# FPGA_Config.net
KiCad netlist of a schematic drawn in Altium Designer
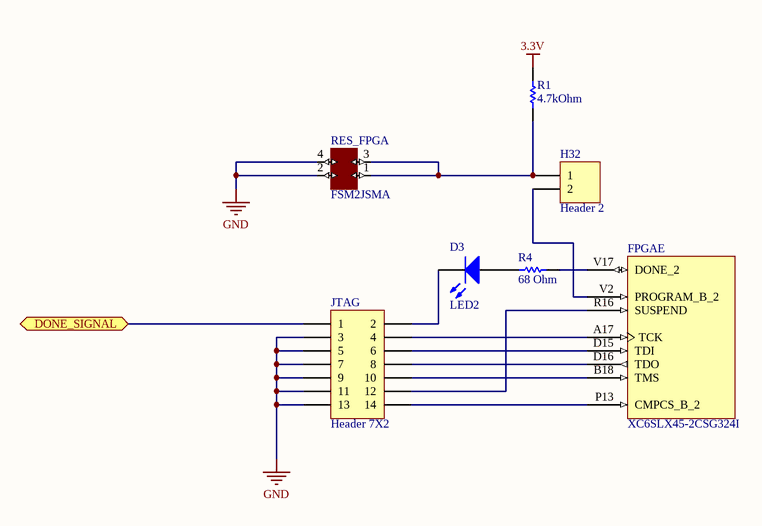
[diagram p0: FPGA Config.SchDoc]

(export (version "E")
  (design (tool "Eeschema 10.0.6"))
  (components
    (comp (ref "D3")
      (value "LED2")
      (footprint "3.2X1.6X1.1")
      (description "Typical RED, GREEN, YELLOW, AMBER GaAs LED")
      (fields (field (name "PUBLISHER") "Altium Limited"))
      (libsource (lib "Miscellaneous Devices") (part "LED2"))
    )
    (comp (ref "FPGA")
      (value "XC6SLX45-2CSG324I")
      (footprint "CSG324")
      (fields (field (name "PUBLISHER") "Altium Limited"))
      (libsource (lib "Xilinx Spartan-6") (part "XC6SLX45-2CSG324I"))
    )
    (comp (ref "H32")
      (value "Header 2")
      (footprint "HDR1X2")
      (description "Header, 2-Pin")
      (fields (field (name "PUBLISHER") "Altium Limited"))
      (libsource (lib "Miscellaneous Connectors") (part "Header 2"))
    )
    (comp (ref "JTAG")
      (value "Header 7X2")
      (footprint "HDR2X7")
      (description "Header, 7-Pin, Dual row")
      (fields (field (name "PUBLISHER") "Altium Limited"))
      (libsource (lib "Miscellaneous Connectors") (part "Header 7X2"))
    )
    (comp (ref "R1")
      (value "4.7kOhm")
      (footprint "RESC0603(1608)_M")
      (description "1R 0.1W 5% 0603 (1608 Metric)  SMD")
      (fields (field (name "POWER") "0.1 W") (field (name "TOLERANCE") "5 %"))
      (libsource (lib "Altium Inc") (part "CMP-1012-00002-1"))
    )
    (comp (ref "R4")
      (value "68 Ohm")
      (footprint "RESC0603(1608)_M")
      (description "1R 0.1W 5% 0603 (1608 Metric)  SMD")
      (fields (field (name "POWER") "0.1 W") (field (name "TOLERANCE") "5 %"))
      (libsource (lib "Altium Content Vault") (part "CMP-1012-00002-1"))
    )
    (comp (ref "RES_FPGA")
      (value "FSM2JSMA")
      (footprint "Button")
      (libsource (lib "Vector Library") (part "switch-button"))
    )
  )
  (nets
    (net (code "1") (name "/DONE_SIGNAL") (class "Default")
      (node (ref "JTAG") (pin "1") (pinfunction "1_1") (pintype "passive"))
    )
    (net (code "2") (name "3.3V") (class "Default")
      (node (ref "R1") (pin "2") (pinfunction "2_2") (pintype "passive"))
    )
    (net (code "3") (name "GND") (class "Default")
      (node (ref "JTAG") (pin "11") (pinfunction "11_11") (pintype "passive"))
      (node (ref "JTAG") (pin "13") (pinfunction "13_13") (pintype "passive"))
      (node (ref "JTAG") (pin "3") (pinfunction "3_3") (pintype "passive"))
      (node (ref "JTAG") (pin "5") (pinfunction "5_5") (pintype "passive"))
      (node (ref "JTAG") (pin "7") (pinfunction "7_7") (pintype "passive"))
      (node (ref "JTAG") (pin "9") (pinfunction "9_9") (pintype "passive"))
      (node (ref "RES_FPGA") (pin "2") (pinfunction "2_2") (pintype "bidirectional"))
      (node (ref "RES_FPGA") (pin "4") (pinfunction "4_4") (pintype "bidirectional"))
    )
    (net (code "4") (name "Net-(D3-A)") (class "Default")
      (node (ref "D3") (pin "1") (pinfunction "A_1") (pintype "passive"))
      (node (ref "R4") (pin "1") (pinfunction "1_1") (pintype "passive"))
    )
    (net (code "5") (name "Net-(D3-K)") (class "Default")
      (node (ref "D3") (pin "2") (pinfunction "K_2") (pintype "passive"))
      (node (ref "JTAG") (pin "2") (pinfunction "2_2") (pintype "passive"))
    )
    (net (code "6") (name "Net-(FPGAE-CMPCS_B_2)") (class "Default")
      (node (ref "FPGA") (pin "P13") (pinfunction "CMPCS_B_2_P13") (pintype "input"))
      (node (ref "JTAG") (pin "14") (pinfunction "14_14") (pintype "passive"))
    )
    (net (code "7") (name "Net-(FPGAE-DONE_2)") (class "Default")
      (node (ref "FPGA") (pin "V17") (pinfunction "DONE_2_V17") (pintype "bidirectional"))
      (node (ref "R4") (pin "2") (pinfunction "2_2") (pintype "passive"))
    )
    (net (code "8") (name "Net-(FPGAE-PROGRAM_B_2)") (class "Default")
      (node (ref "FPGA") (pin "V2") (pinfunction "PROGRAM_B_2_V2") (pintype "input"))
      (node (ref "H32") (pin "2") (pinfunction "2_2") (pintype "passive"))
    )
    (net (code "9") (name "Net-(FPGAE-SUSPEND)") (class "Default")
      (node (ref "FPGA") (pin "R16") (pinfunction "SUSPEND_R16") (pintype "input"))
      (node (ref "JTAG") (pin "12") (pinfunction "12_12") (pintype "passive"))
    )
    (net (code "10") (name "Net-(FPGAE-TCK)") (class "Default")
      (node (ref "FPGA") (pin "A17") (pinfunction "TCK_A17") (pintype "input"))
      (node (ref "JTAG") (pin "4") (pinfunction "4_4") (pintype "passive"))
    )
    (net (code "11") (name "Net-(FPGAE-TDI)") (class "Default")
      (node (ref "FPGA") (pin "D15") (pinfunction "TDI_D15") (pintype "input"))
      (node (ref "JTAG") (pin "6") (pinfunction "6_6") (pintype "passive"))
    )
    (net (code "12") (name "Net-(FPGAE-TDO)") (class "Default")
      (node (ref "FPGA") (pin "D16") (pinfunction "TDO_D16") (pintype "output"))
      (node (ref "JTAG") (pin "8") (pinfunction "8_8") (pintype "passive"))
    )
    (net (code "13") (name "Net-(FPGAE-TMS)") (class "Default")
      (node (ref "FPGA") (pin "B18") (pinfunction "TMS_B18") (pintype "input"))
      (node (ref "JTAG") (pin "10") (pinfunction "10_10") (pintype "passive"))
    )
    (net (code "14") (name "Net-(H32-Pad1)") (class "Default")
      (node (ref "H32") (pin "1") (pinfunction "1_1") (pintype "passive"))
      (node (ref "R1") (pin "1") (pinfunction "1_1") (pintype "passive"))
      (node (ref "RES_FPGA") (pin "1") (pinfunction "1_1") (pintype "bidirectional"))
      (node (ref "RES_FPGA") (pin "3") (pinfunction "3_3") (pintype "bidirectional"))
    )
  )
)
